# dimmer1.net
KiCad netlist of a schematic drawn in EAGLE
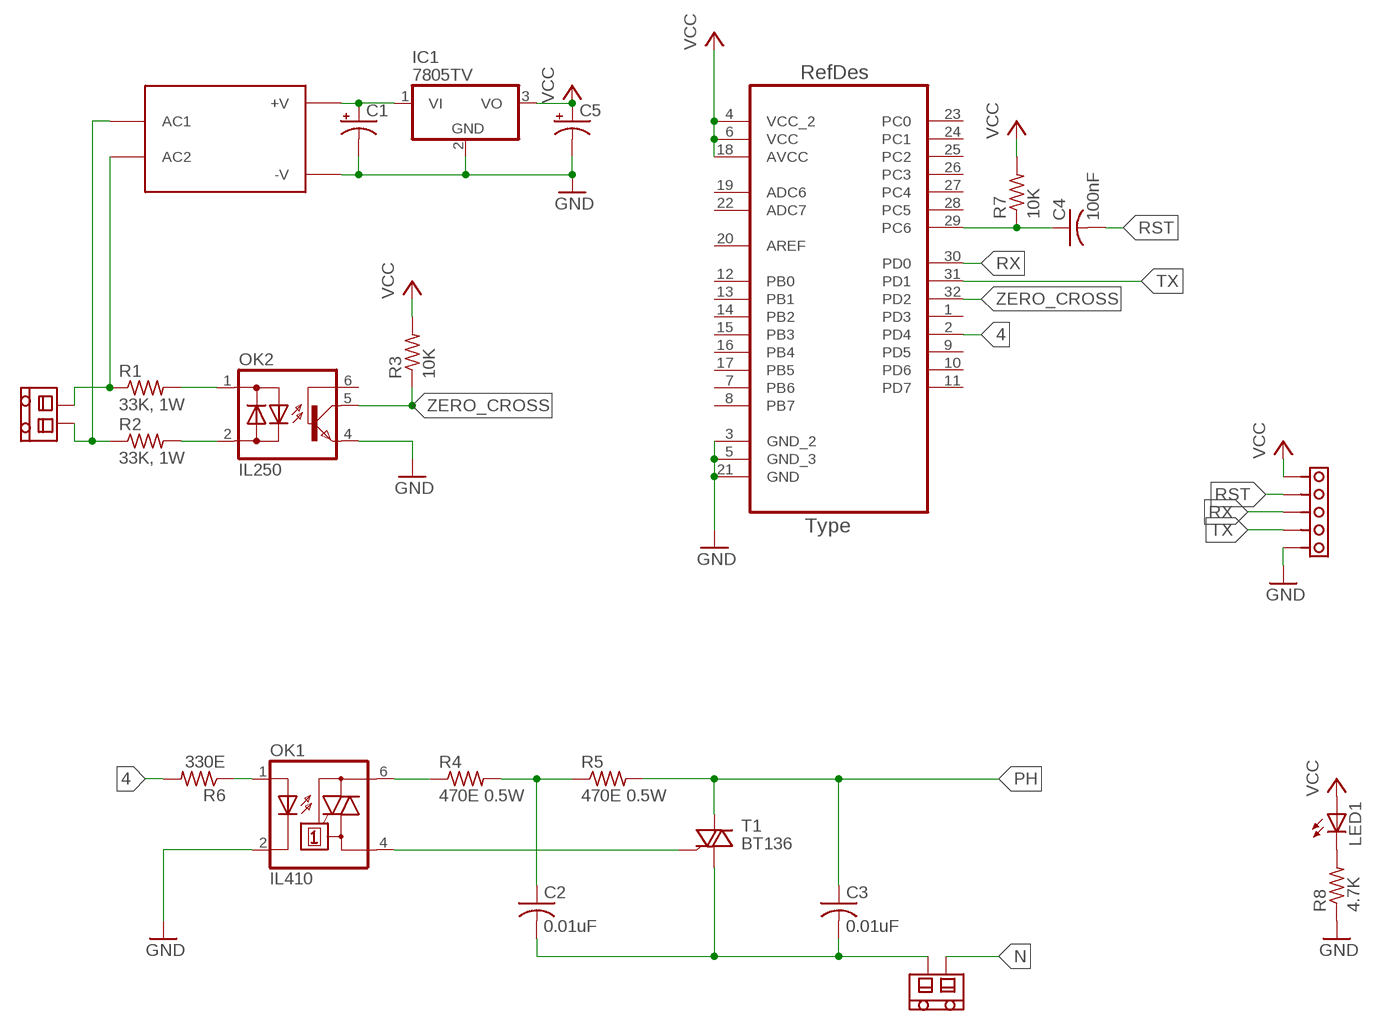
[diagram p0: schematic, sheet 1]

(export (version "E")
  (design (tool "Eeschema 10.0.6"))
  (components
    (comp (ref "C1")
      (value "CPOL-US153CLV-0807")
      (footprint "eagle-import:153CLV-0807")
      (libsource (lib "eagle-import") (part "CPOL-US153CLV-0807"))
    )
    (comp (ref "C2")
      (value "0.01uF")
      (footprint "eagle-import:C075-032X103")
      (libsource (lib "eagle-import") (part "C-US075-032X103"))
    )
    (comp (ref "C3")
      (value "0.01uF")
      (footprint "eagle-import:C075-032X103")
      (libsource (lib "eagle-import") (part "C-US075-032X103"))
    )
    (comp (ref "C4")
      (value "100nF")
      (footprint "eagle-import:C1206")
      (libsource (lib "eagle-import") (part "C-USC1206"))
    )
    (comp (ref "C5")
      (value "CPOL-US153CLV-0807")
      (footprint "eagle-import:153CLV-0807")
      (libsource (lib "eagle-import") (part "CPOL-US153CLV-0807"))
    )
    (comp (ref "IC1")
      (value "7805TV")
      (footprint "eagle-import:TO220V")
      (libsource (lib "eagle-import") (part "78TV05"))
    )
    (comp (ref "LED1")
      (value "LEDCHIPLED_1206")
      (footprint "eagle-import:CHIPLED_1206")
      (libsource (lib "eagle-import") (part "LEDCHIPLED_1206"))
    )
    (comp (ref "OK1")
      (value "IL410")
      (footprint "eagle-import:DIL06")
      (fields (field (name "MF") "VISHAY/TELEFUNKEN"))
      (libsource (lib "eagle-import") (part "IL410"))
    )
    (comp (ref "OK2")
      (value "IL250")
      (footprint "eagle-import:DIL06")
      (fields (field (name "MF") "VISHAY/TELEFUNKEN"))
      (libsource (lib "eagle-import") (part "IL250"))
    )
    (comp (ref "R1")
      (value "33K, 1W")
      (footprint "eagle-import:0207_10")
      (libsource (lib "eagle-import") (part "R-US_0207/10"))
    )
    (comp (ref "R2")
      (value "33K, 1W")
      (footprint "eagle-import:0207_10")
      (libsource (lib "eagle-import") (part "R-US_0207/10"))
    )
    (comp (ref "R3")
      (value "10K")
      (footprint "eagle-import:M1206")
      (libsource (lib "eagle-import") (part "R-US_M1206"))
    )
    (comp (ref "R4")
      (value "470E 0.5W")
      (footprint "eagle-import:0207_12")
      (libsource (lib "eagle-import") (part "R-US_0207/12"))
    )
    (comp (ref "R5")
      (value "470E 0.5W")
      (footprint "eagle-import:0207_12")
      (libsource (lib "eagle-import") (part "R-US_0207/12"))
    )
    (comp (ref "R6")
      (value "330E")
      (footprint "eagle-import:M1206")
      (libsource (lib "eagle-import") (part "R-US_M1206"))
    )
    (comp (ref "R7")
      (value "10K")
      (footprint "eagle-import:M1206")
      (libsource (lib "eagle-import") (part "R-US_M1206"))
    )
    (comp (ref "R8")
      (value "4.7K")
      (footprint "eagle-import:M1206")
      (libsource (lib "eagle-import") (part "R-US_M1206"))
    )
    (comp (ref "T1")
      (value "BT136")
      (footprint "eagle-import:TO220AB")
      (libsource (lib "eagle-import") (part "BT136"))
    )
    (comp (ref "U$1")
      (value "DC_ADAPTER")
      (footprint "eagle-import:DC_ADAPTER")
      (libsource (lib "eagle-import") (part "DC_ADAPTER"))
    )
    (comp (ref "U$2")
      (value "TERMINAL_BLOCK")
      (footprint "eagle-import:TERMINAL_BLOCK")
      (libsource (lib "eagle-import") (part "TERMINAL_BLOCK"))
    )
    (comp (ref "U$3")
      (value "TERMINAL_BLOCK")
      (footprint "eagle-import:TERMINAL_BLOCK")
      (libsource (lib "eagle-import") (part "TERMINAL_BLOCK"))
    )
    (comp (ref "U$4")
      (value "BERG_5")
      (footprint "eagle-import:BERG_5")
      (libsource (lib "eagle-import") (part "BERG_5"))
    )
    (comp (ref "U1")
      (value "ATMEGA328P-AU")
      (footprint "eagle-import:QFP80P900X900X120-32N")
      (libsource (lib "eagle-import") (part "ATMEGA328P-AU"))
    )
  )
  (nets
    (net (code "1") (name "4") (class "Default")
      (node (ref "R6") (pin "2") (pinfunction "2_2") (pintype "passive"))
      (node (ref "U1") (pin "2") (pinfunction "PD4_2") (pintype "bidirectional"))
    )
    (net (code "2") (name "GND") (class "Default")
      (node (ref "C1") (pin "-") (pinfunction "-_-") (pintype "passive"))
      (node (ref "C5") (pin "-") (pinfunction "-_-") (pintype "passive"))
      (node (ref "IC1") (pin "2") (pinfunction "GND_2") (pintype "passive"))
      (node (ref "OK1") (pin "2") (pinfunction "C_2") (pintype "passive"))
      (node (ref "OK2") (pin "4") (pinfunction "E_4") (pintype "passive"))
      (node (ref "R8") (pin "1") (pinfunction "1_1") (pintype "passive"))
      (node (ref "U$1") (pin "V-") (pinfunction "-V_V-") (pintype "bidirectional"))
      (node (ref "U$4") (pin "E") (pinfunction "P$1_E") (pintype "bidirectional"))
      (node (ref "U1") (pin "21") (pinfunction "GND_21") (pintype "passive"))
      (node (ref "U1") (pin "3") (pinfunction "GND_2_3") (pintype "passive"))
      (node (ref "U1") (pin "5") (pinfunction "GND_3_5") (pintype "passive"))
    )
    (net (code "3") (name "N") (class "Default")
      (node (ref "R2") (pin "1") (pinfunction "1_1") (pintype "passive"))
      (node (ref "U$1") (pin "AC1") (pinfunction "AC1_AC1") (pintype "bidirectional"))
      (node (ref "U$2") (pin "1") (pinfunction "P$1_1") (pintype "bidirectional"))
      (node (ref "U$3") (pin "1") (pinfunction "P$1_1") (pintype "bidirectional"))
    )
    (net (code "4") (name "Net-(C2-Pad1)") (class "Default")
      (node (ref "C2") (pin "1") (pinfunction "1_1") (pintype "passive"))
      (node (ref "R4") (pin "2") (pinfunction "2_2") (pintype "passive"))
      (node (ref "R5") (pin "1") (pinfunction "1_1") (pintype "passive"))
    )
    (net (code "5") (name "Net-(IC1-VI)") (class "Default")
      (node (ref "C1") (pin "+") (pinfunction "+_+") (pintype "passive"))
      (node (ref "IC1") (pin "1") (pinfunction "VI_1") (pintype "input"))
      (node (ref "U$1") (pin "V+") (pinfunction "+V_V+") (pintype "bidirectional"))
    )
    (net (code "6") (name "Net-(LED1-PadC)") (class "Default")
      (node (ref "LED1") (pin "C") (pinfunction "C_C") (pintype "passive"))
      (node (ref "R8") (pin "2") (pinfunction "2_2") (pintype "passive"))
    )
    (net (code "7") (name "Net-(OK1-A)") (class "Default")
      (node (ref "OK1") (pin "1") (pinfunction "A_1") (pintype "passive"))
      (node (ref "R6") (pin "1") (pinfunction "1_1") (pintype "passive"))
    )
    (net (code "8") (name "Net-(OK1-A1)") (class "Default")
      (node (ref "OK1") (pin "4") (pinfunction "A1_4") (pintype "passive"))
      (node (ref "T1") (pin "3") (pinfunction "G_3") (pintype "passive"))
    )
    (net (code "9") (name "Net-(OK1-A2)") (class "Default")
      (node (ref "OK1") (pin "6") (pinfunction "A2_6") (pintype "passive"))
      (node (ref "R4") (pin "1") (pinfunction "1_1") (pintype "passive"))
    )
    (net (code "10") (name "Net-(OK2-AC1)") (class "Default")
      (node (ref "OK2") (pin "1") (pinfunction "AC1_1") (pintype "passive"))
      (node (ref "R1") (pin "2") (pinfunction "2_2") (pintype "passive"))
    )
    (net (code "11") (name "Net-(OK2-AC2)") (class "Default")
      (node (ref "OK2") (pin "2") (pinfunction "AC2_2") (pintype "passive"))
      (node (ref "R2") (pin "2") (pinfunction "2_2") (pintype "passive"))
    )
    (net (code "12") (name "Net-(T1-A1)") (class "Default")
      (node (ref "C2") (pin "2") (pinfunction "2_2") (pintype "passive"))
      (node (ref "C3") (pin "2") (pinfunction "2_2") (pintype "passive"))
      (node (ref "T1") (pin "1") (pinfunction "A1_1") (pintype "passive"))
      (node (ref "U$3") (pin "2") (pinfunction "P$2_2") (pintype "bidirectional"))
    )
    (net (code "13") (name "Net-(U1-PC6)") (class "Default")
      (node (ref "C4") (pin "1") (pinfunction "1_1") (pintype "passive"))
      (node (ref "R7") (pin "1") (pinfunction "1_1") (pintype "passive"))
      (node (ref "U1") (pin "29") (pinfunction "PC6_29") (pintype "bidirectional"))
    )
    (net (code "14") (name "PH") (class "Default")
      (node (ref "C3") (pin "1") (pinfunction "1_1") (pintype "passive"))
      (node (ref "R1") (pin "1") (pinfunction "1_1") (pintype "passive"))
      (node (ref "R5") (pin "2") (pinfunction "2_2") (pintype "passive"))
      (node (ref "T1") (pin "2") (pinfunction "A2_2") (pintype "passive"))
      (node (ref "U$1") (pin "AC2") (pinfunction "AC2_AC2") (pintype "bidirectional"))
      (node (ref "U$2") (pin "2") (pinfunction "P$2_2") (pintype "bidirectional"))
    )
    (net (code "15") (name "RST") (class "Default")
      (node (ref "C4") (pin "2") (pinfunction "2_2") (pintype "passive"))
      (node (ref "U$4") (pin "H") (pinfunction "P$4_H") (pintype "bidirectional"))
    )
    (net (code "16") (name "RX") (class "Default")
      (node (ref "U$4") (pin "G") (pinfunction "P$3_G") (pintype "bidirectional"))
      (node (ref "U1") (pin "30") (pinfunction "PD0_30") (pintype "bidirectional"))
    )
    (net (code "17") (name "TX") (class "Default")
      (node (ref "U$4") (pin "F") (pinfunction "P$2_F") (pintype "bidirectional"))
      (node (ref "U1") (pin "31") (pinfunction "PD1_31") (pintype "bidirectional"))
    )
    (net (code "18") (name "VCC") (class "Default")
      (node (ref "C5") (pin "+") (pinfunction "+_+") (pintype "passive"))
      (node (ref "IC1") (pin "3") (pinfunction "VO_3") (pintype "passive"))
      (node (ref "LED1") (pin "A") (pinfunction "A_A") (pintype "passive"))
      (node (ref "R3") (pin "2") (pinfunction "2_2") (pintype "passive"))
      (node (ref "R7") (pin "2") (pinfunction "2_2") (pintype "passive"))
      (node (ref "U$4") (pin "I") (pinfunction "P$5_I") (pintype "bidirectional"))
      (node (ref "U1") (pin "18") (pinfunction "AVCC_18") (pintype "power_in"))
      (node (ref "U1") (pin "4") (pinfunction "VCC_2_4") (pintype "power_in"))
      (node (ref "U1") (pin "6") (pinfunction "VCC_6") (pintype "power_in"))
    )
    (net (code "19") (name "ZERO_CROSS") (class "Default")
      (node (ref "OK2") (pin "5") (pinfunction "C_5") (pintype "passive"))
      (node (ref "R3") (pin "1") (pinfunction "1_1") (pintype "passive"))
      (node (ref "U1") (pin "32") (pinfunction "PD2_32") (pintype "bidirectional"))
    )
    (net (code "20") (name "unconnected-(OK2-B-Pad6)") (class "Default")
      (node (ref "OK2") (pin "6") (pinfunction "B_6") (pintype "passive"))
    )
    (net (code "21") (name "unconnected-(U1-ADC6-Pad19)") (class "Default")
      (node (ref "U1") (pin "19") (pinfunction "ADC6_19") (pintype "input"))
    )
    (net (code "22") (name "unconnected-(U1-ADC7-Pad22)") (class "Default")
      (node (ref "U1") (pin "22") (pinfunction "ADC7_22") (pintype "input"))
    )
    (net (code "23") (name "unconnected-(U1-AREF-Pad20)") (class "Default")
      (node (ref "U1") (pin "20") (pinfunction "AREF_20") (pintype "input"))
    )
    (net (code "24") (name "unconnected-(U1-PB0-Pad12)") (class "Default")
      (node (ref "U1") (pin "12") (pinfunction "PB0_12") (pintype "bidirectional"))
    )
    (net (code "25") (name "unconnected-(U1-PB1-Pad13)") (class "Default")
      (node (ref "U1") (pin "13") (pinfunction "PB1_13") (pintype "bidirectional"))
    )
    (net (code "26") (name "unconnected-(U1-PB2-Pad14)") (class "Default")
      (node (ref "U1") (pin "14") (pinfunction "PB2_14") (pintype "bidirectional"))
    )
    (net (code "27") (name "unconnected-(U1-PB3-Pad15)") (class "Default")
      (node (ref "U1") (pin "15") (pinfunction "PB3_15") (pintype "bidirectional"))
    )
    (net (code "28") (name "unconnected-(U1-PB4-Pad16)") (class "Default")
      (node (ref "U1") (pin "16") (pinfunction "PB4_16") (pintype "bidirectional"))
    )
    (net (code "29") (name "unconnected-(U1-PB5-Pad17)") (class "Default")
      (node (ref "U1") (pin "17") (pinfunction "PB5_17") (pintype "bidirectional"))
    )
    (net (code "30") (name "unconnected-(U1-PB6-Pad7)") (class "Default")
      (node (ref "U1") (pin "7") (pinfunction "PB6_7") (pintype "bidirectional"))
    )
    (net (code "31") (name "unconnected-(U1-PB7-Pad8)") (class "Default")
      (node (ref "U1") (pin "8") (pinfunction "PB7_8") (pintype "bidirectional"))
    )
    (net (code "32") (name "unconnected-(U1-PC0-Pad23)") (class "Default")
      (node (ref "U1") (pin "23") (pinfunction "PC0_23") (pintype "bidirectional"))
    )
    (net (code "33") (name "unconnected-(U1-PC1-Pad24)") (class "Default")
      (node (ref "U1") (pin "24") (pinfunction "PC1_24") (pintype "bidirectional"))
    )
    (net (code "34") (name "unconnected-(U1-PC2-Pad25)") (class "Default")
      (node (ref "U1") (pin "25") (pinfunction "PC2_25") (pintype "bidirectional"))
    )
    (net (code "35") (name "unconnected-(U1-PC3-Pad26)") (class "Default")
      (node (ref "U1") (pin "26") (pinfunction "PC3_26") (pintype "bidirectional"))
    )
    (net (code "36") (name "unconnected-(U1-PC4-Pad27)") (class "Default")
      (node (ref "U1") (pin "27") (pinfunction "PC4_27") (pintype "bidirectional"))
    )
    (net (code "37") (name "unconnected-(U1-PC5-Pad28)") (class "Default")
      (node (ref "U1") (pin "28") (pinfunction "PC5_28") (pintype "bidirectional"))
    )
    (net (code "38") (name "unconnected-(U1-PD3-Pad1)") (class "Default")
      (node (ref "U1") (pin "1") (pinfunction "PD3_1") (pintype "bidirectional"))
    )
    (net (code "39") (name "unconnected-(U1-PD5-Pad9)") (class "Default")
      (node (ref "U1") (pin "9") (pinfunction "PD5_9") (pintype "bidirectional"))
    )
    (net (code "40") (name "unconnected-(U1-PD6-Pad10)") (class "Default")
      (node (ref "U1") (pin "10") (pinfunction "PD6_10") (pintype "bidirectional"))
    )
    (net (code "41") (name "unconnected-(U1-PD7-Pad11)") (class "Default")
      (node (ref "U1") (pin "11") (pinfunction "PD7_11") (pintype "bidirectional"))
    )
  )
)
